# stm32f103_ethernet_shield_2.net
KiCad netlist of a schematic drawn in EAGLE
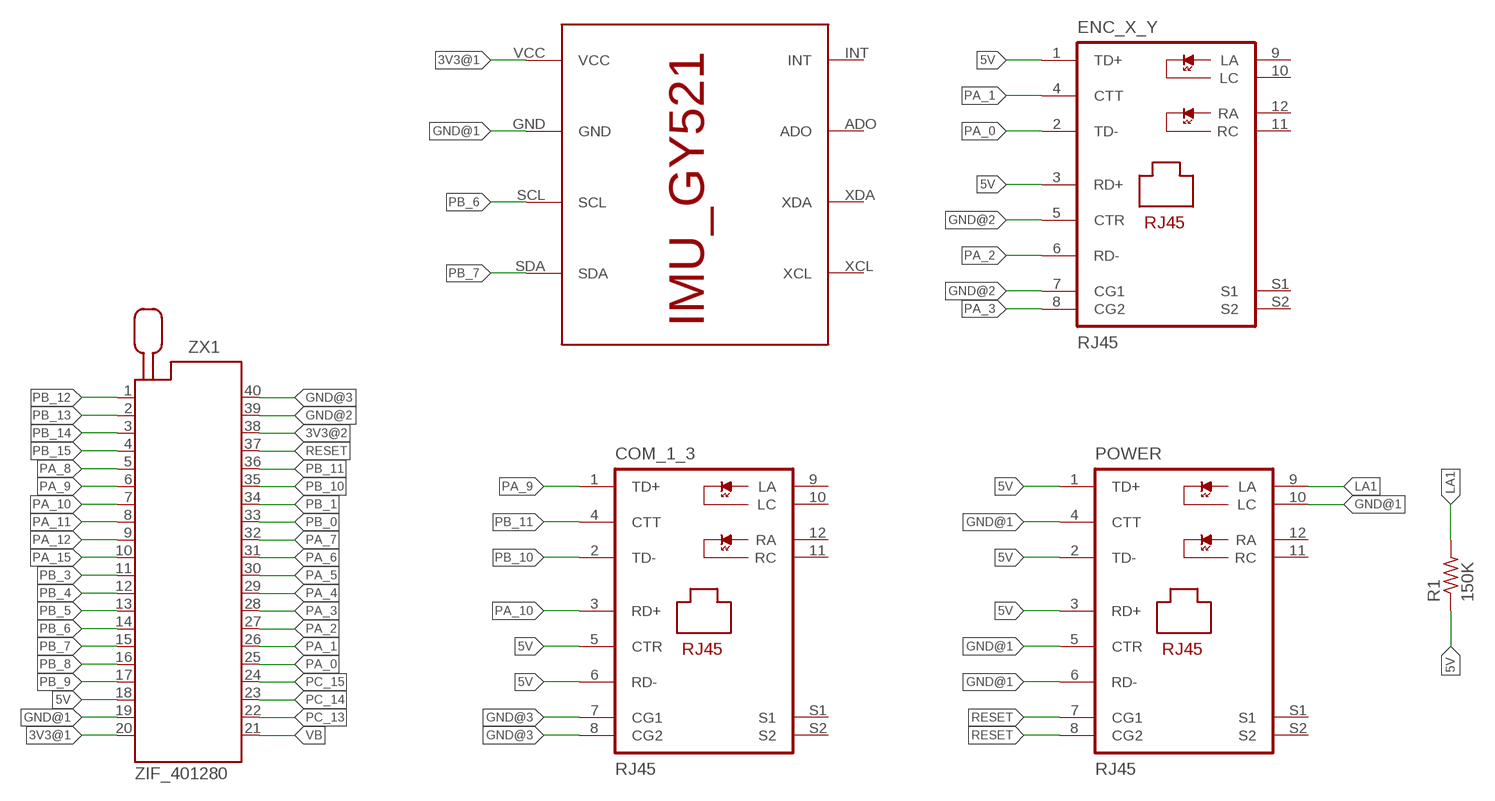
[diagram p0: schematic, sheet 1]

(export (version "E")
  (design (tool "Eeschema 10.0.6"))
  (components
    (comp (ref "COM_1_3")
      (value "RJ45")
      (footprint "eagle-import:J0-A_B_F")
      (libsource (lib "eagle-import") (part "RJ45_METAL_LEDS"))
    )
    (comp (ref "ENC_X_Y")
      (value "RJ45")
      (footprint "eagle-import:J0-A_B_F")
      (fields (field (name "SPICEPREFIX") "X"))
      (libsource (lib "eagle-import") (part "RJ45_METAL_LEDS"))
    )
    (comp (ref "MPU6050")
      (value "IMU_ROBOCON_GY521")
      (footprint "eagle-import:IMU_GY521")
      (libsource (lib "eagle-import") (part "IMU_ROBOCON_GY521"))
    )
    (comp (ref "POWER")
      (value "RJ45")
      (footprint "eagle-import:J0-A_B_F")
      (libsource (lib "eagle-import") (part "RJ45_METAL_LEDS"))
    )
    (comp (ref "R1")
      (value "150K")
      (footprint "eagle-import:0204_7")
      (libsource (lib "eagle-import") (part "RES-7"))
    )
    (comp (ref "ZX1")
      (value "ZIF_401280")
      (footprint "eagle-import:240-1280-00-0602J")
      (libsource (lib "eagle-import") (part "ZIF_401280"))
    )
  )
  (nets
    (net (code "1") (name "3V3@1") (class "Default")
      (node (ref "MPU6050") (pin "VCC") (pinfunction "VCC_VCC") (pintype "bidirectional"))
      (node (ref "ZX1") (pin "20") (pinfunction "20_20") (pintype "passive"))
    )
    (net (code "2") (name "3V3@2") (class "Default")
      (node (ref "ZX1") (pin "38") (pinfunction "38_38") (pintype "passive"))
    )
    (net (code "3") (name "5V") (class "Default")
      (node (ref "COM_1_3") (pin "5") (pinfunction "CTR_5") (pintype "passive"))
      (node (ref "COM_1_3") (pin "6") (pinfunction "RD-_6") (pintype "passive"))
      (node (ref "ENC_X_Y") (pin "1") (pinfunction "TD+_1") (pintype "passive"))
      (node (ref "ENC_X_Y") (pin "3") (pinfunction "RD+_3") (pintype "passive"))
      (node (ref "POWER") (pin "1") (pinfunction "TD+_1") (pintype "passive"))
      (node (ref "POWER") (pin "2") (pinfunction "TD-_2") (pintype "passive"))
      (node (ref "POWER") (pin "3") (pinfunction "RD+_3") (pintype "passive"))
      (node (ref "R1") (pin "1") (pinfunction "1_1") (pintype "passive"))
      (node (ref "ZX1") (pin "18") (pinfunction "18_18") (pintype "passive"))
    )
    (net (code "4") (name "GND@1") (class "Default")
      (node (ref "MPU6050") (pin "GND") (pinfunction "GND_GND") (pintype "bidirectional"))
      (node (ref "POWER") (pin "10") (pinfunction "LC_10") (pintype "passive"))
      (node (ref "POWER") (pin "4") (pinfunction "CTT_4") (pintype "passive"))
      (node (ref "POWER") (pin "5") (pinfunction "CTR_5") (pintype "passive"))
      (node (ref "POWER") (pin "6") (pinfunction "RD-_6") (pintype "passive"))
      (node (ref "ZX1") (pin "19") (pinfunction "19_19") (pintype "passive"))
    )
    (net (code "5") (name "GND@2") (class "Default")
      (node (ref "ENC_X_Y") (pin "5") (pinfunction "CTR_5") (pintype "passive"))
      (node (ref "ENC_X_Y") (pin "7") (pinfunction "CG1_7") (pintype "passive"))
      (node (ref "ZX1") (pin "39") (pinfunction "39_39") (pintype "passive"))
    )
    (net (code "6") (name "GND@3") (class "Default")
      (node (ref "COM_1_3") (pin "7") (pinfunction "CG1_7") (pintype "passive"))
      (node (ref "COM_1_3") (pin "8") (pinfunction "CG2_8") (pintype "passive"))
      (node (ref "ZX1") (pin "40") (pinfunction "40_40") (pintype "passive"))
    )
    (net (code "7") (name "LA1") (class "Default")
      (node (ref "POWER") (pin "9") (pinfunction "LA_9") (pintype "passive"))
      (node (ref "R1") (pin "2") (pinfunction "2_2") (pintype "passive"))
    )
    (net (code "8") (name "PA_0") (class "Default")
      (node (ref "ENC_X_Y") (pin "2") (pinfunction "TD-_2") (pintype "passive"))
      (node (ref "ZX1") (pin "25") (pinfunction "25_25") (pintype "passive"))
    )
    (net (code "9") (name "PA_1") (class "Default")
      (node (ref "ENC_X_Y") (pin "4") (pinfunction "CTT_4") (pintype "passive"))
      (node (ref "ZX1") (pin "26") (pinfunction "26_26") (pintype "passive"))
    )
    (net (code "10") (name "PA_2") (class "Default")
      (node (ref "ENC_X_Y") (pin "6") (pinfunction "RD-_6") (pintype "passive"))
      (node (ref "ZX1") (pin "27") (pinfunction "27_27") (pintype "passive"))
    )
    (net (code "11") (name "PA_3") (class "Default")
      (node (ref "ENC_X_Y") (pin "8") (pinfunction "CG2_8") (pintype "passive"))
      (node (ref "ZX1") (pin "28") (pinfunction "28_28") (pintype "passive"))
    )
    (net (code "12") (name "PA_4") (class "Default")
      (node (ref "ZX1") (pin "29") (pinfunction "29_29") (pintype "passive"))
    )
    (net (code "13") (name "PA_5") (class "Default")
      (node (ref "ZX1") (pin "30") (pinfunction "30_30") (pintype "passive"))
    )
    (net (code "14") (name "PA_6") (class "Default")
      (node (ref "ZX1") (pin "31") (pinfunction "31_31") (pintype "passive"))
    )
    (net (code "15") (name "PA_7") (class "Default")
      (node (ref "ZX1") (pin "32") (pinfunction "32_32") (pintype "passive"))
    )
    (net (code "16") (name "PA_8") (class "Default")
      (node (ref "ZX1") (pin "5") (pinfunction "5_5") (pintype "passive"))
    )
    (net (code "17") (name "PA_9") (class "Default")
      (node (ref "COM_1_3") (pin "1") (pinfunction "TD+_1") (pintype "passive"))
      (node (ref "ZX1") (pin "6") (pinfunction "6_6") (pintype "passive"))
    )
    (net (code "18") (name "PA_10") (class "Default")
      (node (ref "COM_1_3") (pin "3") (pinfunction "RD+_3") (pintype "passive"))
      (node (ref "ZX1") (pin "7") (pinfunction "7_7") (pintype "passive"))
    )
    (net (code "19") (name "PA_11") (class "Default")
      (node (ref "ZX1") (pin "8") (pinfunction "8_8") (pintype "passive"))
    )
    (net (code "20") (name "PA_12") (class "Default")
      (node (ref "ZX1") (pin "9") (pinfunction "9_9") (pintype "passive"))
    )
    (net (code "21") (name "PA_15") (class "Default")
      (node (ref "ZX1") (pin "10") (pinfunction "10_10") (pintype "passive"))
    )
    (net (code "22") (name "PB_0") (class "Default")
      (node (ref "ZX1") (pin "33") (pinfunction "33_33") (pintype "passive"))
    )
    (net (code "23") (name "PB_1") (class "Default")
      (node (ref "ZX1") (pin "34") (pinfunction "34_34") (pintype "passive"))
    )
    (net (code "24") (name "PB_3") (class "Default")
      (node (ref "ZX1") (pin "11") (pinfunction "11_11") (pintype "passive"))
    )
    (net (code "25") (name "PB_4") (class "Default")
      (node (ref "ZX1") (pin "12") (pinfunction "12_12") (pintype "passive"))
    )
    (net (code "26") (name "PB_5") (class "Default")
      (node (ref "ZX1") (pin "13") (pinfunction "13_13") (pintype "passive"))
    )
    (net (code "27") (name "PB_6") (class "Default")
      (node (ref "MPU6050") (pin "SCL") (pinfunction "SCL_SCL") (pintype "bidirectional"))
      (node (ref "ZX1") (pin "14") (pinfunction "14_14") (pintype "passive"))
    )
    (net (code "28") (name "PB_7") (class "Default")
      (node (ref "MPU6050") (pin "SDA") (pinfunction "SDA_SDA") (pintype "bidirectional"))
      (node (ref "ZX1") (pin "15") (pinfunction "15_15") (pintype "passive"))
    )
    (net (code "29") (name "PB_8") (class "Default")
      (node (ref "ZX1") (pin "16") (pinfunction "16_16") (pintype "passive"))
    )
    (net (code "30") (name "PB_9") (class "Default")
      (node (ref "ZX1") (pin "17") (pinfunction "17_17") (pintype "passive"))
    )
    (net (code "31") (name "PB_10") (class "Default")
      (node (ref "COM_1_3") (pin "2") (pinfunction "TD-_2") (pintype "passive"))
      (node (ref "ZX1") (pin "35") (pinfunction "35_35") (pintype "passive"))
    )
    (net (code "32") (name "PB_11") (class "Default")
      (node (ref "COM_1_3") (pin "4") (pinfunction "CTT_4") (pintype "passive"))
      (node (ref "ZX1") (pin "36") (pinfunction "36_36") (pintype "passive"))
    )
    (net (code "33") (name "PB_12") (class "Default")
      (node (ref "ZX1") (pin "1") (pinfunction "1_1") (pintype "passive"))
    )
    (net (code "34") (name "PB_13") (class "Default")
      (node (ref "ZX1") (pin "2") (pinfunction "2_2") (pintype "passive"))
    )
    (net (code "35") (name "PB_14") (class "Default")
      (node (ref "ZX1") (pin "3") (pinfunction "3_3") (pintype "passive"))
    )
    (net (code "36") (name "PB_15") (class "Default")
      (node (ref "ZX1") (pin "4") (pinfunction "4_4") (pintype "passive"))
    )
    (net (code "37") (name "PC_13") (class "Default")
      (node (ref "ZX1") (pin "22") (pinfunction "22_22") (pintype "passive"))
    )
    (net (code "38") (name "PC_14") (class "Default")
      (node (ref "ZX1") (pin "23") (pinfunction "23_23") (pintype "passive"))
    )
    (net (code "39") (name "PC_15") (class "Default")
      (node (ref "ZX1") (pin "24") (pinfunction "24_24") (pintype "passive"))
    )
    (net (code "40") (name "RESET") (class "Default")
      (node (ref "POWER") (pin "7") (pinfunction "CG1_7") (pintype "passive"))
      (node (ref "POWER") (pin "8") (pinfunction "CG2_8") (pintype "passive"))
      (node (ref "ZX1") (pin "37") (pinfunction "37_37") (pintype "passive"))
    )
    (net (code "41") (name "VB") (class "Default")
      (node (ref "ZX1") (pin "21") (pinfunction "21_21") (pintype "passive"))
    )
    (net (code "42") (name "unconnected-(COM_1_3-LA-Pad9)") (class "Default")
      (node (ref "COM_1_3") (pin "9") (pinfunction "LA_9") (pintype "passive"))
    )
    (net (code "43") (name "unconnected-(COM_1_3-LC-Pad10)") (class "Default")
      (node (ref "COM_1_3") (pin "10") (pinfunction "LC_10") (pintype "passive"))
    )
    (net (code "44") (name "unconnected-(COM_1_3-PadS1)") (class "Default")
      (node (ref "COM_1_3") (pin "S1") (pinfunction "S1_S1") (pintype "passive"))
    )
    (net (code "45") (name "unconnected-(COM_1_3-PadS2)") (class "Default")
      (node (ref "COM_1_3") (pin "S2") (pinfunction "S2_S2") (pintype "passive"))
    )
    (net (code "46") (name "unconnected-(COM_1_3-RA-Pad12)") (class "Default")
      (node (ref "COM_1_3") (pin "12") (pinfunction "RA_12") (pintype "passive"))
    )
    (net (code "47") (name "unconnected-(COM_1_3-RC-Pad11)") (class "Default")
      (node (ref "COM_1_3") (pin "11") (pinfunction "RC_11") (pintype "passive"))
    )
    (net (code "48") (name "unconnected-(ENC_X_Y-LA-Pad9)") (class "Default")
      (node (ref "ENC_X_Y") (pin "9") (pinfunction "LA_9") (pintype "passive"))
    )
    (net (code "49") (name "unconnected-(ENC_X_Y-LC-Pad10)") (class "Default")
      (node (ref "ENC_X_Y") (pin "10") (pinfunction "LC_10") (pintype "passive"))
    )
    (net (code "50") (name "unconnected-(ENC_X_Y-PadS1)") (class "Default")
      (node (ref "ENC_X_Y") (pin "S1") (pinfunction "S1_S1") (pintype "passive"))
    )
    (net (code "51") (name "unconnected-(ENC_X_Y-PadS2)") (class "Default")
      (node (ref "ENC_X_Y") (pin "S2") (pinfunction "S2_S2") (pintype "passive"))
    )
    (net (code "52") (name "unconnected-(ENC_X_Y-RA-Pad12)") (class "Default")
      (node (ref "ENC_X_Y") (pin "12") (pinfunction "RA_12") (pintype "passive"))
    )
    (net (code "53") (name "unconnected-(ENC_X_Y-RC-Pad11)") (class "Default")
      (node (ref "ENC_X_Y") (pin "11") (pinfunction "RC_11") (pintype "passive"))
    )
    (net (code "54") (name "unconnected-(MPU6050-PadADO)") (class "Default")
      (node (ref "MPU6050") (pin "ADO") (pinfunction "ADO_ADO") (pintype "bidirectional"))
    )
    (net (code "55") (name "unconnected-(MPU6050-PadINT)") (class "Default")
      (node (ref "MPU6050") (pin "INT") (pinfunction "INT_INT") (pintype "bidirectional"))
    )
    (net (code "56") (name "unconnected-(MPU6050-PadXCL)") (class "Default")
      (node (ref "MPU6050") (pin "XCL") (pinfunction "XCL_XCL") (pintype "bidirectional"))
    )
    (net (code "57") (name "unconnected-(MPU6050-PadXDA)") (class "Default")
      (node (ref "MPU6050") (pin "XDA") (pinfunction "XDA_XDA") (pintype "bidirectional"))
    )
    (net (code "58") (name "unconnected-(POWER-PadS1)") (class "Default")
      (node (ref "POWER") (pin "S1") (pinfunction "S1_S1") (pintype "passive"))
    )
    (net (code "59") (name "unconnected-(POWER-PadS2)") (class "Default")
      (node (ref "POWER") (pin "S2") (pinfunction "S2_S2") (pintype "passive"))
    )
    (net (code "60") (name "unconnected-(POWER-RA-Pad12)") (class "Default")
      (node (ref "POWER") (pin "12") (pinfunction "RA_12") (pintype "passive"))
    )
    (net (code "61") (name "unconnected-(POWER-RC-Pad11)") (class "Default")
      (node (ref "POWER") (pin "11") (pinfunction "RC_11") (pintype "passive"))
    )
  )
)
